# DCC_fDecoder.net
KiCad netlist of a schematic drawn in EAGLE
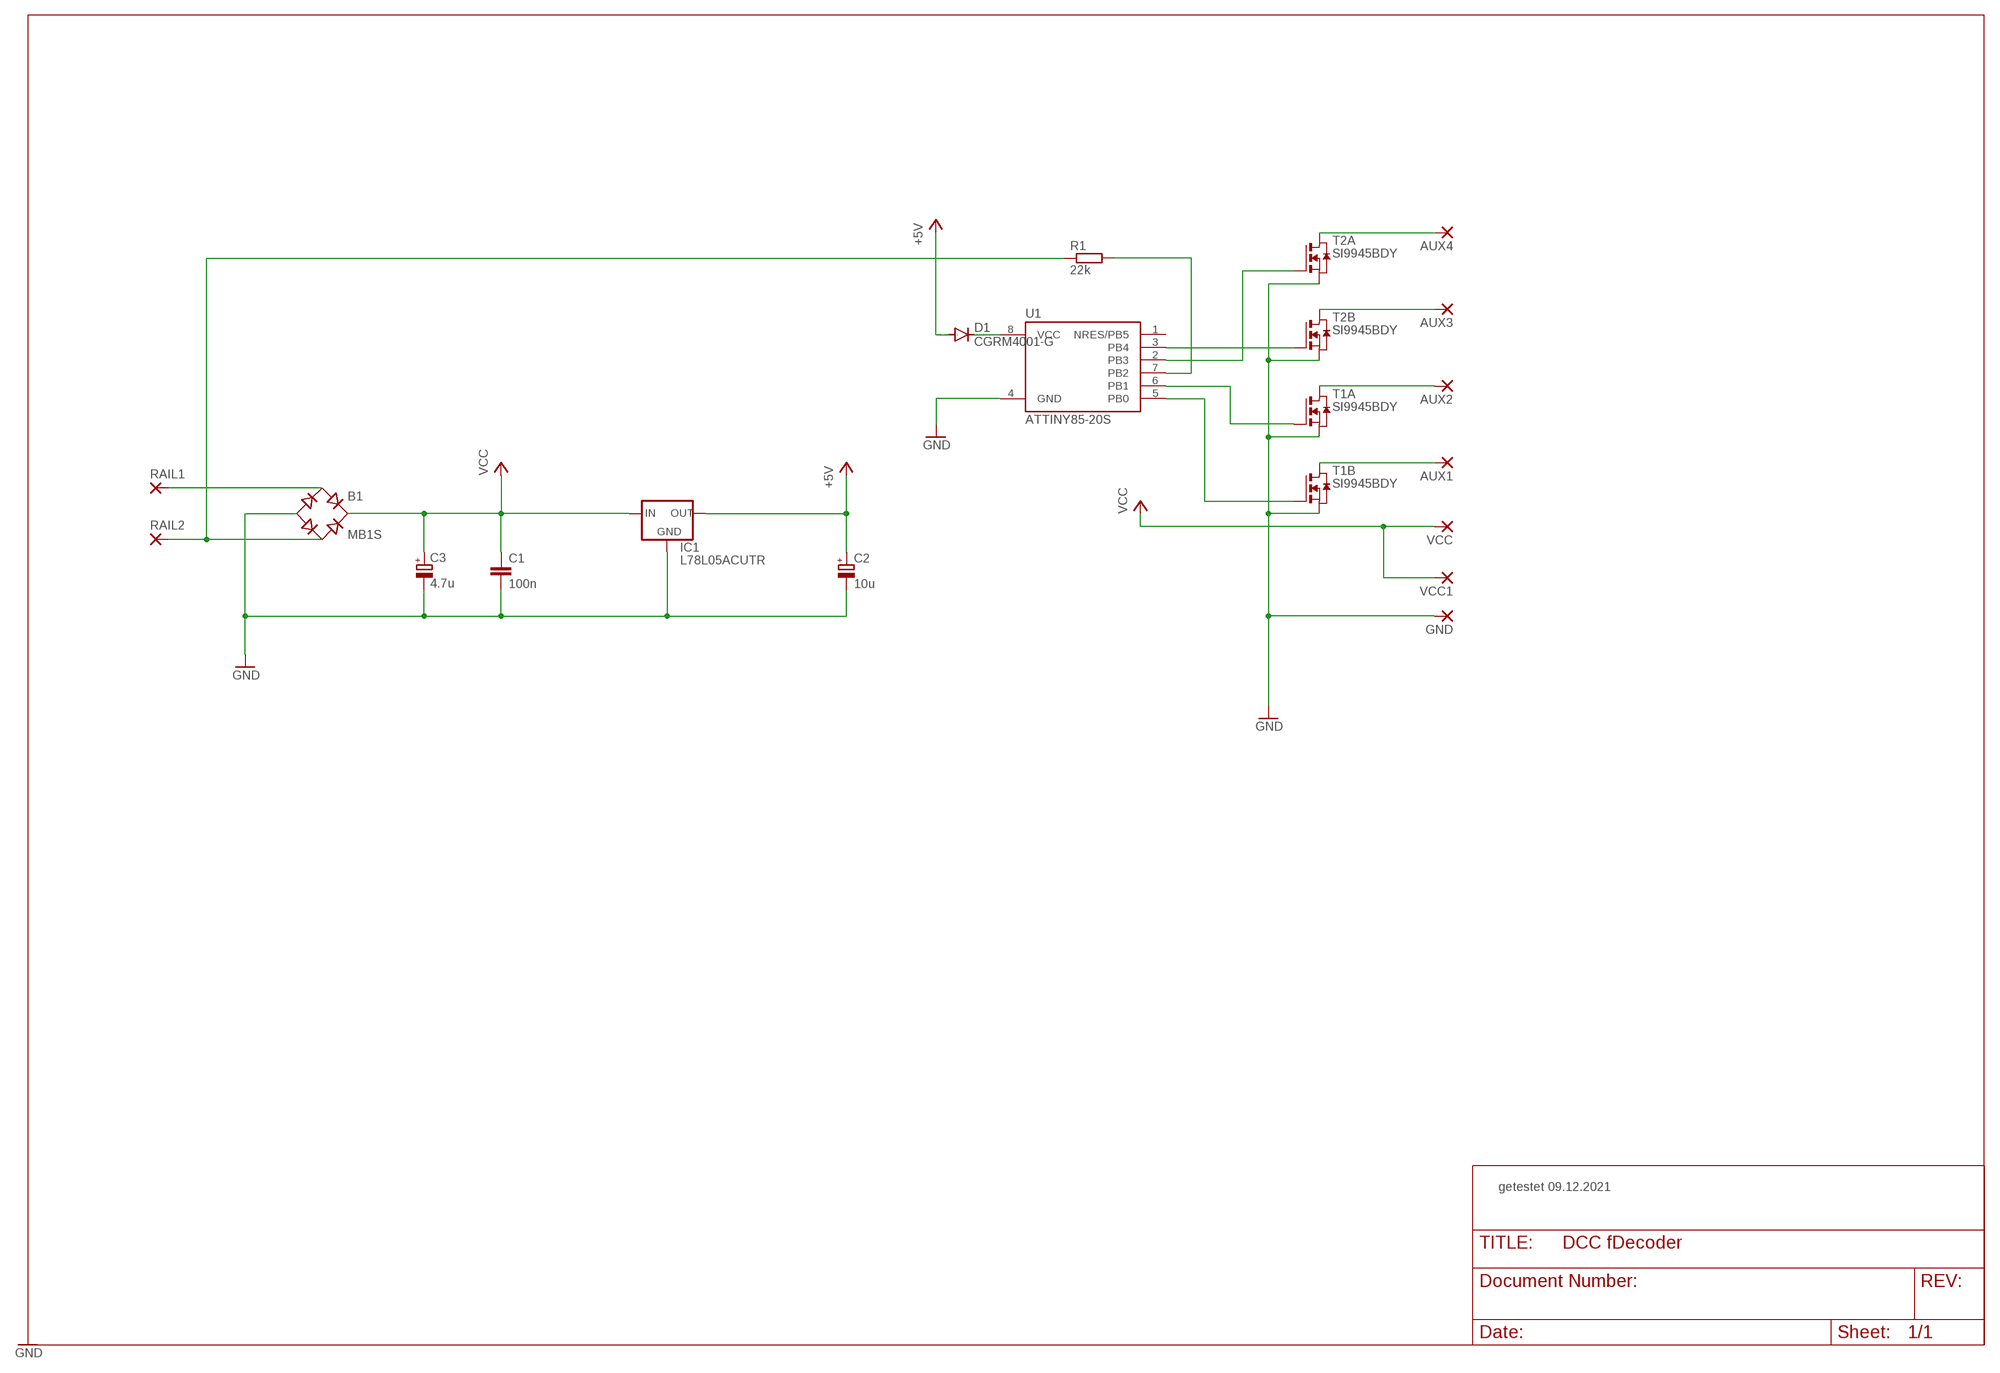
[diagram p0: schematic, sheet 1]

(export (version "E")
  (design (tool "Eeschema 10.0.6"))
  (components
    (comp (ref "AUX1")
      (value "SMD2")
      (footprint "eagle-import:SMD1,27-2,54")
      (libsource (lib "eagle-import") (part "SMD2"))
    )
    (comp (ref "AUX2")
      (value "SMD2")
      (footprint "eagle-import:SMD1,27-2,54")
      (libsource (lib "eagle-import") (part "SMD2"))
    )
    (comp (ref "AUX3")
      (value "SMD2")
      (footprint "eagle-import:SMD1,27-2,54")
      (libsource (lib "eagle-import") (part "SMD2"))
    )
    (comp (ref "AUX4")
      (value "SMD2")
      (footprint "eagle-import:SMD1,27-2,54")
      (libsource (lib "eagle-import") (part "SMD2"))
    )
    (comp (ref "B1")
      (value "MB1S")
      (footprint "eagle-import:SOIC-4")
      (libsource (lib "eagle-import") (part "MBS1"))
    )
    (comp (ref "C1")
      (value "100n")
      (footprint "eagle-import:C0805")
      (libsource (lib "eagle-import") (part "C-EUC0805"))
    )
    (comp (ref "C2")
      (value "10u")
      (footprint "eagle-import:A_3216-18W")
      (libsource (lib "eagle-import") (part "CPOL-EUA/3216-18W"))
    )
    (comp (ref "C3")
      (value "4.7u")
      (footprint "eagle-import:A_3216-18W")
      (libsource (lib "eagle-import") (part "CPOL-EUA/3216-18W"))
    )
    (comp (ref "D1")
      (value "CGRM4001-G")
      (footprint "eagle-import:SOD-123_MINI-SMA")
      (libsource (lib "eagle-import") (part "CGRM400-G1"))
    )
    (comp (ref "GND")
      (value "SMD2")
      (footprint "eagle-import:SMD1,27-2,54")
      (libsource (lib "eagle-import") (part "SMD2"))
    )
    (comp (ref "IC1")
      (value "L78L05ACUTR")
      (footprint "eagle-import:SOT89R")
      (libsource (lib "eagle-import") (part "L78L05ACUTR"))
    )
    (comp (ref "R1")
      (value "22k")
      (footprint "eagle-import:R0805")
      (libsource (lib "eagle-import") (part "R-EU_R0805"))
    )
    (comp (ref "RAIL1")
      (value "SMD2")
      (footprint "eagle-import:SMD1,27-2,54")
      (libsource (lib "eagle-import") (part "SMD2"))
    )
    (comp (ref "RAIL2")
      (value "SMD2")
      (footprint "eagle-import:SMD1,27-2,54")
      (libsource (lib "eagle-import") (part "SMD2"))
    )
    (comp (ref "T1")
      (value "SI9945BDY")
      (footprint "eagle-import:SO8")
      (libsource (lib "eagle-import") (part "NMOS2SO8"))
    )
    (comp (ref "T2")
      (value "SI9945BDY")
      (footprint "eagle-import:SO8")
      (libsource (lib "eagle-import") (part "NMOS2SO8"))
    )
    (comp (ref "U1")
      (value "ATTINY85-20S")
      (footprint "eagle-import:SOIC8_EIAJ_208MIL")
      (libsource (lib "eagle-import") (part "ATTINY85S-20"))
    )
    (comp (ref "VCC")
      (value "SMD2")
      (footprint "eagle-import:SMD1,27-2,54")
      (libsource (lib "eagle-import") (part "SMD2"))
    )
    (comp (ref "VCC1")
      (value "SMD2")
      (footprint "eagle-import:SMD1,27-2,54")
      (libsource (lib "eagle-import") (part "SMD2"))
    )
  )
  (nets
    (net (code "1") (name "+5V") (class "Default")
      (node (ref "C2") (pin "+") (pinfunction "+_+") (pintype "passive"))
      (node (ref "D1") (pin "A") (pinfunction "A_A") (pintype "passive"))
      (node (ref "IC1") (pin "2") (pinfunction "OUT_2") (pintype "passive"))
    )
    (net (code "2") (name "GND") (class "Default")
      (node (ref "B1") (pin "-") (pinfunction "-_-") (pintype "passive"))
      (node (ref "C1") (pin "2") (pinfunction "2_2") (pintype "passive"))
      (node (ref "C2") (pin "-") (pinfunction "-_-") (pintype "passive"))
      (node (ref "C3") (pin "-") (pinfunction "-_-") (pintype "passive"))
      (node (ref "GND") (pin "1") (pinfunction "P_1") (pintype "passive"))
      (node (ref "IC1") (pin "3") (pinfunction "GND_3") (pintype "input"))
      (node (ref "IC1") (pin "4") (pinfunction "GND_4") (pintype "input"))
      (node (ref "T1") (pin "1") (pinfunction "S_1") (pintype "passive"))
      (node (ref "T1") (pin "3") (pinfunction "S_3") (pintype "passive"))
      (node (ref "T2") (pin "1") (pinfunction "S_1") (pintype "passive"))
      (node (ref "T2") (pin "3") (pinfunction "S_3") (pintype "passive"))
      (node (ref "U1") (pin "4") (pinfunction "GND_4") (pintype "power_in"))
    )
    (net (code "3") (name "Net-(AUX1-P)") (class "Default")
      (node (ref "AUX1") (pin "1") (pinfunction "P_1") (pintype "passive"))
      (node (ref "T1") (pin "5") (pinfunction "D_5") (pintype "passive"))
      (node (ref "T1") (pin "6") (pinfunction "D_6") (pintype "passive"))
    )
    (net (code "4") (name "Net-(AUX2-P)") (class "Default")
      (node (ref "AUX2") (pin "1") (pinfunction "P_1") (pintype "passive"))
      (node (ref "T1") (pin "7") (pinfunction "D_7") (pintype "passive"))
      (node (ref "T1") (pin "8") (pinfunction "D_8") (pintype "passive"))
    )
    (net (code "5") (name "Net-(AUX3-P)") (class "Default")
      (node (ref "AUX3") (pin "1") (pinfunction "P_1") (pintype "passive"))
      (node (ref "T2") (pin "5") (pinfunction "D_5") (pintype "passive"))
      (node (ref "T2") (pin "6") (pinfunction "D_6") (pintype "passive"))
    )
    (net (code "6") (name "Net-(AUX4-P)") (class "Default")
      (node (ref "AUX4") (pin "1") (pinfunction "P_1") (pintype "passive"))
      (node (ref "T2") (pin "7") (pinfunction "D_7") (pintype "passive"))
      (node (ref "T2") (pin "8") (pinfunction "D_8") (pintype "passive"))
    )
    (net (code "7") (name "Net-(B1-AC1)") (class "Default")
      (node (ref "B1") (pin "~1") (pinfunction "AC1_~1") (pintype "passive"))
      (node (ref "RAIL1") (pin "1") (pinfunction "P_1") (pintype "passive"))
    )
    (net (code "8") (name "Net-(B1-AC2)") (class "Default")
      (node (ref "B1") (pin "~2") (pinfunction "AC2_~2") (pintype "passive"))
      (node (ref "R1") (pin "1") (pinfunction "1_1") (pintype "passive"))
      (node (ref "RAIL2") (pin "1") (pinfunction "P_1") (pintype "passive"))
    )
    (net (code "9") (name "Net-(T1A-G)") (class "Default")
      (node (ref "T1") (pin "2") (pinfunction "G_2") (pintype "passive"))
      (node (ref "U1") (pin "6") (pinfunction "PB1_6") (pintype "bidirectional"))
    )
    (net (code "10") (name "Net-(T1B-G)") (class "Default")
      (node (ref "T1") (pin "4") (pinfunction "G_4") (pintype "passive"))
      (node (ref "U1") (pin "5") (pinfunction "PB0_5") (pintype "bidirectional"))
    )
    (net (code "11") (name "Net-(T2A-G)") (class "Default")
      (node (ref "T2") (pin "2") (pinfunction "G_2") (pintype "passive"))
      (node (ref "U1") (pin "2") (pinfunction "PB3_2") (pintype "bidirectional"))
    )
    (net (code "12") (name "Net-(T2B-G)") (class "Default")
      (node (ref "T2") (pin "4") (pinfunction "G_4") (pintype "passive"))
      (node (ref "U1") (pin "3") (pinfunction "PB4_3") (pintype "bidirectional"))
    )
    (net (code "13") (name "Net-(U1-PB2)") (class "Default")
      (node (ref "R1") (pin "2") (pinfunction "2_2") (pintype "passive"))
      (node (ref "U1") (pin "7") (pinfunction "PB2_7") (pintype "bidirectional"))
    )
    (net (code "14") (name "Net-(U1-VCC)") (class "Default")
      (node (ref "D1") (pin "C") (pinfunction "C_C") (pintype "passive"))
      (node (ref "U1") (pin "8") (pinfunction "VCC_8") (pintype "power_in"))
    )
    (net (code "15") (name "VCC") (class "Default")
      (node (ref "B1") (pin "+") (pinfunction "+_+") (pintype "passive"))
      (node (ref "C1") (pin "1") (pinfunction "1_1") (pintype "passive"))
      (node (ref "C3") (pin "+") (pinfunction "+_+") (pintype "passive"))
      (node (ref "IC1") (pin "1") (pinfunction "IN_1") (pintype "input"))
      (node (ref "VCC") (pin "1") (pinfunction "P_1") (pintype "passive"))
      (node (ref "VCC1") (pin "1") (pinfunction "P_1") (pintype "passive"))
    )
    (net (code "16") (name "unconnected-(U1-NRES{slash}PB5-Pad1)") (class "Default")
      (node (ref "U1") (pin "1") (pinfunction "NRES/PB5_1") (pintype "bidirectional"))
    )
  )
)
